# 03_Connectors.net
KiCad netlist of a schematic drawn in Altium Designer
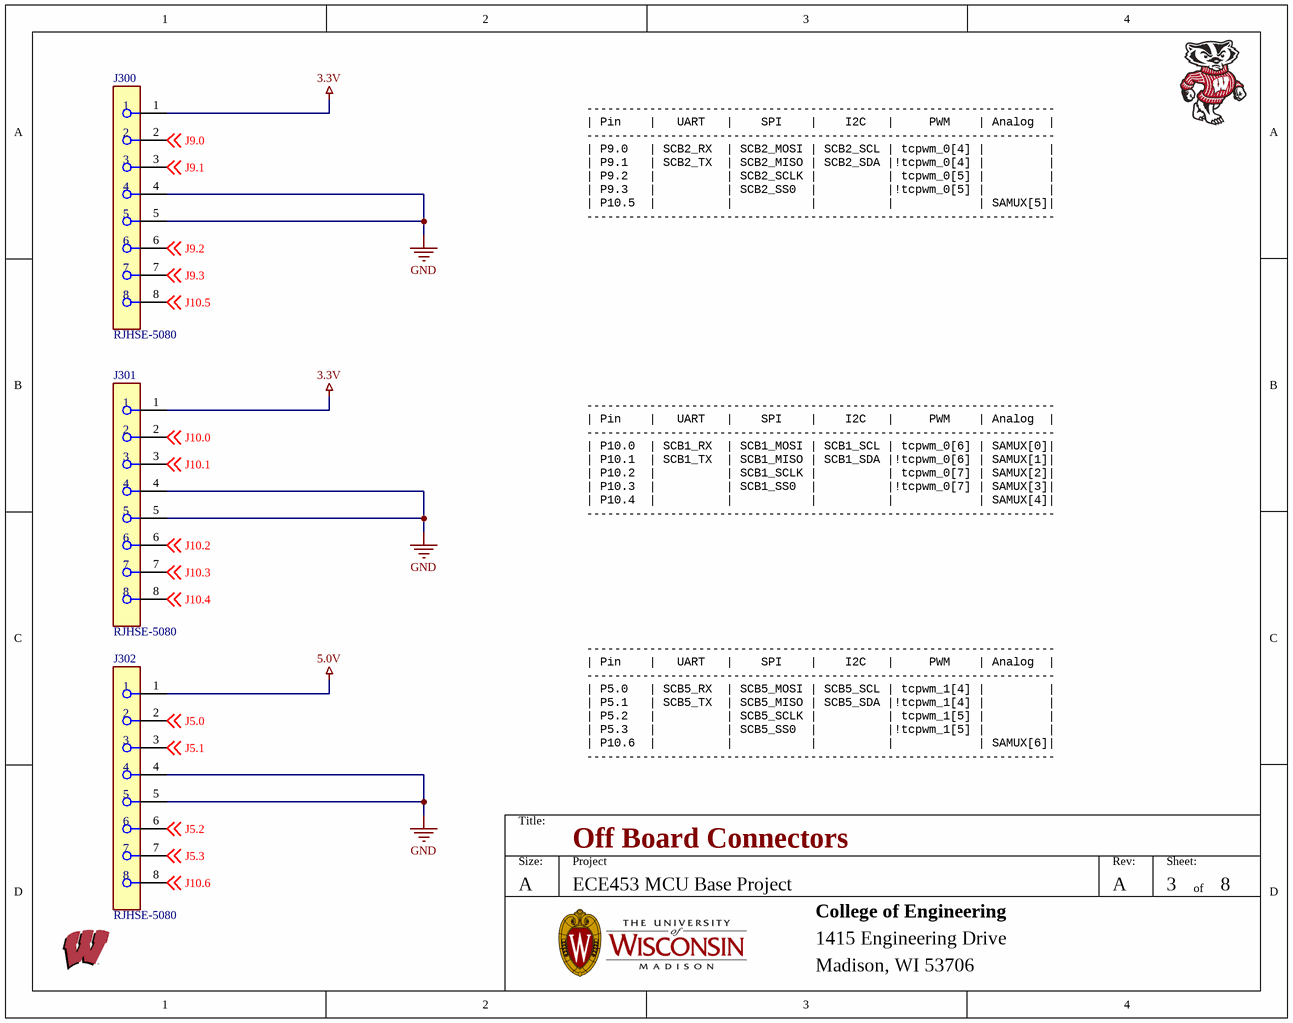
[diagram p0: 03_Connectors.SchDoc]

(export (version "E")
  (design (tool "Eeschema 10.0.6"))
  (components
    (comp (ref "J300")
      (value "RJHSE-5080")
      (footprint "FP-RJHSE-5080-MFG")
      (description "CONN MOD JACK 8P8C R/A UNSHLD")
      (fields
        (field (name "OCTOPART") "https://octopart.com/rjhse-5080-amphenol-45060")
        (field (name "MANUFACTURER") "Amphenol")
      )
      (libsource (lib "Altium Content Vault") (part "b0a0b555dd3abf3683e7c330df25cc4"))
    )
    (comp (ref "J301")
      (value "RJHSE-5080")
      (footprint "FP-RJHSE-5080-MFG")
      (description "CONN MOD JACK 8P8C R/A UNSHLD")
      (fields
        (field (name "OCTOPART") "https://octopart.com/rjhse-5080-amphenol-45060")
        (field (name "MANUFACTURER") "Amphenol")
      )
      (libsource (lib "Altium Content Vault") (part "b0a0b555dd3abf3683e7c330df25cc4"))
    )
    (comp (ref "J302")
      (value "RJHSE-5080")
      (footprint "FP-RJHSE-5080-MFG")
      (description "CONN MOD JACK 8P8C R/A UNSHLD")
      (fields
        (field (name "OCTOPART") "https://octopart.com/rjhse-5080-amphenol-45060")
        (field (name "MANUFACTURER") "Amphenol")
      )
      (libsource (lib "Altium Content Vault") (part "b0a0b555dd3abf3683e7c330df25cc4"))
    )
  )
  (nets
    (net (code "1") (name "3.3V") (class "Default")
      (node (ref "J300") (pin "1") (pinfunction "1_1") (pintype "passive"))
      (node (ref "J301") (pin "1") (pinfunction "1_1") (pintype "passive"))
    )
    (net (code "2") (name "5.0V") (class "Default")
      (node (ref "J302") (pin "1") (pinfunction "1_1") (pintype "passive"))
    )
    (net (code "3") (name "GND") (class "Default")
      (node (ref "J300") (pin "4") (pinfunction "4_4") (pintype "passive"))
      (node (ref "J300") (pin "5") (pinfunction "5_5") (pintype "passive"))
      (node (ref "J301") (pin "4") (pinfunction "4_4") (pintype "passive"))
      (node (ref "J301") (pin "5") (pinfunction "5_5") (pintype "passive"))
      (node (ref "J302") (pin "4") (pinfunction "4_4") (pintype "passive"))
      (node (ref "J302") (pin "5") (pinfunction "5_5") (pintype "passive"))
    )
    (net (code "4") (name "J5.0") (class "Default")
      (node (ref "J302") (pin "2") (pinfunction "2_2") (pintype "passive"))
    )
    (net (code "5") (name "J5.1") (class "Default")
      (node (ref "J302") (pin "3") (pinfunction "3_3") (pintype "passive"))
    )
    (net (code "6") (name "J5.2") (class "Default")
      (node (ref "J302") (pin "6") (pinfunction "6_6") (pintype "passive"))
    )
    (net (code "7") (name "J5.3") (class "Default")
      (node (ref "J302") (pin "7") (pinfunction "7_7") (pintype "passive"))
    )
    (net (code "8") (name "J9.0") (class "Default")
      (node (ref "J300") (pin "2") (pinfunction "2_2") (pintype "passive"))
    )
    (net (code "9") (name "J9.1") (class "Default")
      (node (ref "J300") (pin "3") (pinfunction "3_3") (pintype "passive"))
    )
    (net (code "10") (name "J9.2") (class "Default")
      (node (ref "J300") (pin "6") (pinfunction "6_6") (pintype "passive"))
    )
    (net (code "11") (name "J9.3") (class "Default")
      (node (ref "J300") (pin "7") (pinfunction "7_7") (pintype "passive"))
    )
    (net (code "12") (name "J10.0") (class "Default")
      (node (ref "J301") (pin "2") (pinfunction "2_2") (pintype "passive"))
    )
    (net (code "13") (name "J10.1") (class "Default")
      (node (ref "J301") (pin "3") (pinfunction "3_3") (pintype "passive"))
    )
    (net (code "14") (name "J10.2") (class "Default")
      (node (ref "J301") (pin "6") (pinfunction "6_6") (pintype "passive"))
    )
    (net (code "15") (name "J10.3") (class "Default")
      (node (ref "J301") (pin "7") (pinfunction "7_7") (pintype "passive"))
    )
    (net (code "16") (name "J10.4") (class "Default")
      (node (ref "J301") (pin "8") (pinfunction "8_8") (pintype "passive"))
    )
    (net (code "17") (name "J10.5") (class "Default")
      (node (ref "J300") (pin "8") (pinfunction "8_8") (pintype "passive"))
    )
    (net (code "18") (name "J10.6") (class "Default")
      (node (ref "J302") (pin "8") (pinfunction "8_8") (pintype "passive"))
    )
  )
)
